# Domino_USB_MicroSD_Passive_Overcurrent_P.net
KiCad netlist of a schematic drawn in EAGLE
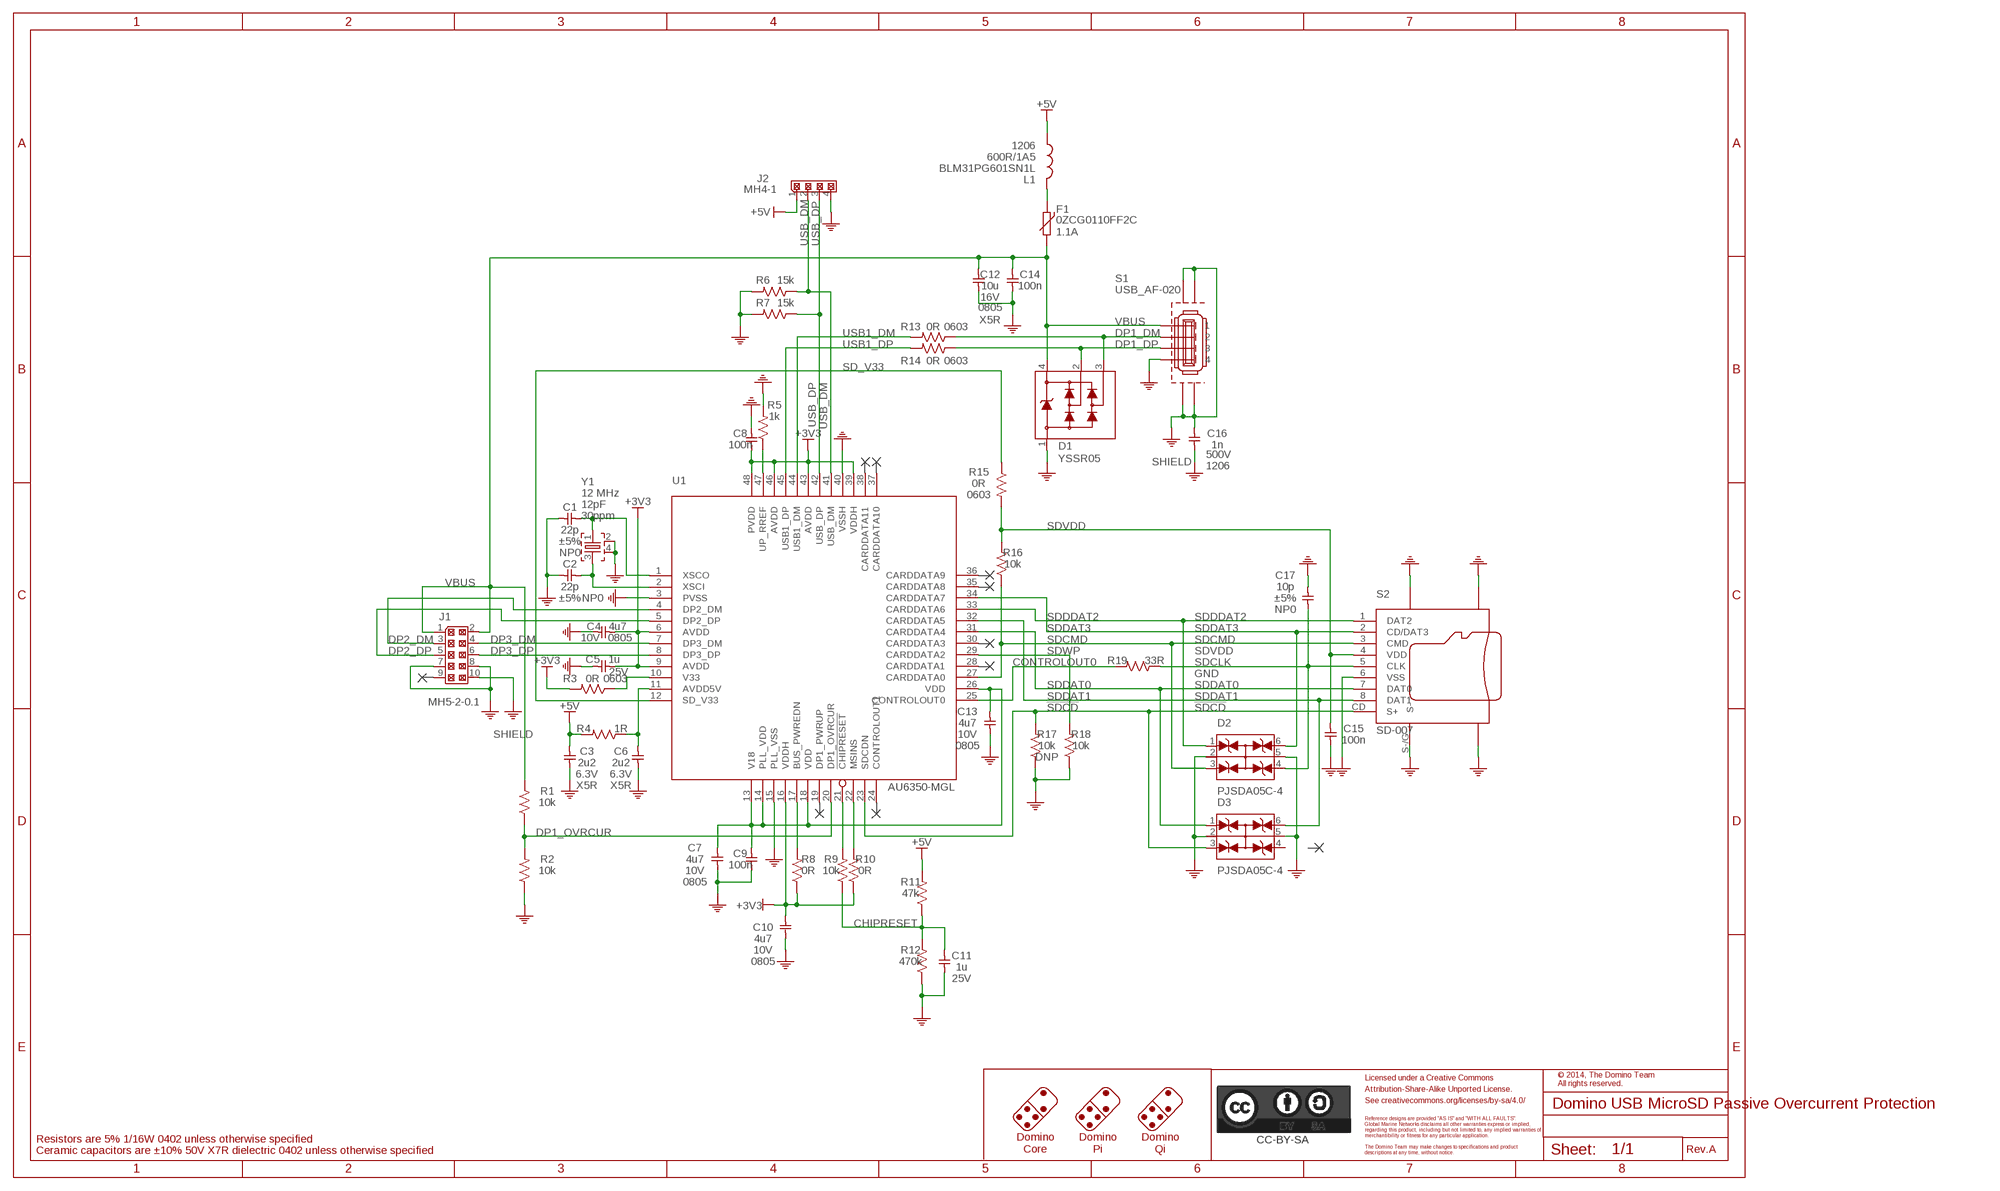
[diagram p0: schematic, sheet 1]

(export (version "E")
  (design (tool "Eeschema 10.0.6"))
  (components
    (comp (ref "C1")
      (value "22p")
      (footprint "eagle-import:C0402")
      (fields
        (field (name "PARTNO") "C0402_22p_NP0_5%_CER_50V")
        (field (name "TC") "NP0")
        (field (name "TOL") "±5%")
      )
      (libsource (lib "eagle-import") (part "CAP_0402"))
    )
    (comp (ref "C2")
      (value "22p")
      (footprint "eagle-import:C0402")
      (fields
        (field (name "PARTNO") "C0402_22p_NP0_5%_CER_50V")
        (field (name "TC") "NP0")
        (field (name "TOL") "±5%")
      )
      (libsource (lib "eagle-import") (part "CAP_0402"))
    )
    (comp (ref "C3")
      (value "2u2")
      (footprint "eagle-import:C0402")
      (fields
        (field (name "PARTNO") "C0402_2u2_X5R_10%_CER_6V3")
        (field (name "TC") "X5R")
        (field (name "VOLT") "6.3V")
      )
      (libsource (lib "eagle-import") (part "CAP_0402"))
    )
    (comp (ref "C4")
      (value "4u7")
      (footprint "eagle-import:C0805")
      (fields
        (field (name "SIZE") "0805")
        (field (name "PARTNO") "C0805_4u7_X7R_10%_CER_6V3")
        (field (name "VOLT") "10V")
      )
      (libsource (lib "eagle-import") (part "CAP_0805"))
    )
    (comp (ref "C5")
      (value "1u")
      (footprint "eagle-import:C0402")
      (fields (field (name "PARTNO") "C0402_1u_X7R_10%_CER_25V") (field (name "VOLT") "25V"))
      (libsource (lib "eagle-import") (part "CAP_0402"))
    )
    (comp (ref "C6")
      (value "2u2")
      (footprint "eagle-import:C0402")
      (fields
        (field (name "PARTNO") "C0402_2u2_X5R_10%_CER_6V3")
        (field (name "TC") "X5R")
        (field (name "VOLT") "6.3V")
      )
      (libsource (lib "eagle-import") (part "CAP_0402"))
    )
    (comp (ref "C7")
      (value "4u7")
      (footprint "eagle-import:C0805")
      (fields
        (field (name "SIZE") "0805")
        (field (name "PARTNO") "C0805_4u7_X7R_10%_CER_6V3")
        (field (name "VOLT") "10V")
      )
      (libsource (lib "eagle-import") (part "CAP_0805"))
    )
    (comp (ref "C8")
      (value "100n")
      (footprint "eagle-import:C0402")
      (fields (field (name "PARTNO") "C0402_100n_X7R_10%_CER_50V"))
      (libsource (lib "eagle-import") (part "CAP_0402"))
    )
    (comp (ref "C9")
      (value "100n")
      (footprint "eagle-import:C0402")
      (fields (field (name "PARTNO") "C0402_100n_X7R_10%_CER_50V"))
      (libsource (lib "eagle-import") (part "CAP_0402"))
    )
    (comp (ref "C10")
      (value "4u7")
      (footprint "eagle-import:C0805")
      (fields
        (field (name "SIZE") "0805")
        (field (name "PARTNO") "C0805_4u7_X7R_10%_CER_6V3")
        (field (name "VOLT") "10V")
      )
      (libsource (lib "eagle-import") (part "CAP_0805"))
    )
    (comp (ref "C11")
      (value "1u")
      (footprint "eagle-import:C0402")
      (fields (field (name "PARTNO") "C0402_1u_X7R_10%_CER_25V") (field (name "VOLT") "25V"))
      (libsource (lib "eagle-import") (part "CAP_0402"))
    )
    (comp (ref "C12")
      (value "10u")
      (footprint "eagle-import:C0805")
      (fields
        (field (name "SIZE") "0805")
        (field (name "PARTNO") "C0805_10u_X5R_10%_CER_16V")
        (field (name "TC") "X5R")
        (field (name "VOLT") "16V")
      )
      (libsource (lib "eagle-import") (part "CAP_0805"))
    )
    (comp (ref "C13")
      (value "4u7")
      (footprint "eagle-import:C0805")
      (fields
        (field (name "SIZE") "0805")
        (field (name "PARTNO") "C0805_4u7_X7R_10%_CER_6V3")
        (field (name "VOLT") "10V")
      )
      (libsource (lib "eagle-import") (part "CAP_0805"))
    )
    (comp (ref "C14")
      (value "100n")
      (footprint "eagle-import:C0402")
      (fields (field (name "PARTNO") "C0402_100n_X7R_10%_CER_50V"))
      (libsource (lib "eagle-import") (part "CAP_0402"))
    )
    (comp (ref "C15")
      (value "100n")
      (footprint "eagle-import:C0402")
      (fields (field (name "PARTNO") "C0402_100n_X7R_10%_CER_50V"))
      (libsource (lib "eagle-import") (part "CAP_0402"))
    )
    (comp (ref "C16")
      (value "1n")
      (footprint "eagle-import:C1206")
      (fields
        (field (name "SIZE") "1206")
        (field (name "PARTNO") "C1206_1n_X7R_10%_CER_500V")
        (field (name "VOLT") "500V")
      )
      (libsource (lib "eagle-import") (part "CAP_1206"))
    )
    (comp (ref "C17")
      (value "10p")
      (footprint "eagle-import:C0402")
      (fields
        (field (name "PARTNO") "C0402_10p_NP0_5%_CER_50V")
        (field (name "TC") "NP0")
        (field (name "TOL") "±5%")
      )
      (libsource (lib "eagle-import") (part "CAP_0402"))
    )
    (comp (ref "CC-BY-SA1")
      (value "CC-BY-SA_LOGO")
      (footprint "eagle-import:CC-BY-SA_LOGO")
      (libsource (lib "eagle-import") (part "CC-BY-SA_LOGO"))
    )
    (comp (ref "D1")
      (value "YSSR05")
      (footprint "eagle-import:SOT143B")
      (libsource (lib "eagle-import") (part "YSSR05"))
    )
    (comp (ref "D2")
      (value "PJSDA05C-4")
      (footprint "eagle-import:SOT23-6")
      (libsource (lib "eagle-import") (part "PJSDA05C-4"))
    )
    (comp (ref "D3")
      (value "PJSDA05C-4")
      (footprint "eagle-import:SOT23-6")
      (libsource (lib "eagle-import") (part "PJSDA05C-4"))
    )
    (comp (ref "F1")
      (value "0ZCG0110FF2C")
      (footprint "eagle-import:PTC1812")
      (fields (field (name "RATE") "1.1A"))
      (libsource (lib "eagle-import") (part "0ZCG0110FF2C"))
    )
    (comp (ref "J1")
      (value "MH5-2-0.1")
      (footprint "eagle-import:MH05-2-0.1")
      (libsource (lib "eagle-import") (part "MH5-2"))
    )
    (comp (ref "J2")
      (value "MH4-1")
      (footprint "eagle-import:MH4-1-0.1")
      (fields (field (name "PARTNO") "MH4-1-0.1"))
      (libsource (lib "eagle-import") (part "MH4-1"))
    )
    (comp (ref "L1")
      (value "BLM31PG601SN1L")
      (footprint "eagle-import:FB1206")
      (fields (field (name "SIZE") "1206") (field (name "OPT") "600R/1A5"))
      (libsource (lib "eagle-import") (part "FB_1206"))
    )
    (comp (ref "R1")
      (value "10k")
      (footprint "eagle-import:R0402")
      (fields (field (name "PARTNO") "R0402_10k_5%_62.5mW"))
      (libsource (lib "eagle-import") (part "RES_0402"))
    )
    (comp (ref "R2")
      (value "10k")
      (footprint "eagle-import:R0402")
      (fields (field (name "PARTNO") "R0402_10k_5%_62.5mW"))
      (libsource (lib "eagle-import") (part "RES_0402"))
    )
    (comp (ref "R3")
      (value "0R")
      (footprint "eagle-import:R0603")
      (fields (field (name "SIZE") "0603") (field (name "PARTNO") "R0603_0R_5%_125mW"))
      (libsource (lib "eagle-import") (part "RES_0603"))
    )
    (comp (ref "R4")
      (value "1R")
      (footprint "eagle-import:R0402")
      (fields (field (name "PARTNO") "R0402_1R_5%_62.5mW"))
      (libsource (lib "eagle-import") (part "RES_0402"))
    )
    (comp (ref "R5")
      (value "1k")
      (footprint "eagle-import:R0402")
      (fields (field (name "PARTNO") "R0402_1k_5%_62.5mW"))
      (libsource (lib "eagle-import") (part "RES_0402"))
    )
    (comp (ref "R6")
      (value "15k")
      (footprint "eagle-import:R0402")
      (fields (field (name "PARTNO") "R0402_15k_5%_62.5mW"))
      (libsource (lib "eagle-import") (part "RES_0402"))
    )
    (comp (ref "R7")
      (value "15k")
      (footprint "eagle-import:R0402")
      (fields (field (name "PARTNO") "R0402_15k_5%_62.5mW"))
      (libsource (lib "eagle-import") (part "RES_0402"))
    )
    (comp (ref "R8")
      (value "0R")
      (footprint "eagle-import:R0402")
      (fields (field (name "PARTNO") "R0402_0R_5%_62.5mW"))
      (libsource (lib "eagle-import") (part "RES_0402"))
    )
    (comp (ref "R9")
      (value "10k")
      (footprint "eagle-import:R0402")
      (fields (field (name "PARTNO") "R0402_10k_5%_62.5mW"))
      (libsource (lib "eagle-import") (part "RES_0402"))
    )
    (comp (ref "R10")
      (value "0R")
      (footprint "eagle-import:R0402")
      (fields (field (name "PARTNO") "R0402_0R_5%_62.5mW"))
      (libsource (lib "eagle-import") (part "RES_0402"))
    )
    (comp (ref "R11")
      (value "47k")
      (footprint "eagle-import:R0402")
      (fields (field (name "PARTNO") "R0402_47k_5%_62.5mW"))
      (libsource (lib "eagle-import") (part "RES_0402"))
    )
    (comp (ref "R12")
      (value "470k")
      (footprint "eagle-import:R0402")
      (fields (field (name "PARTNO") "R0402_470k_5%_62.5mW"))
      (libsource (lib "eagle-import") (part "RES_0402"))
    )
    (comp (ref "R13")
      (value "0R")
      (footprint "eagle-import:R0603")
      (fields (field (name "SIZE") "0603") (field (name "PARTNO") "R0603_0R_5%_125mW"))
      (libsource (lib "eagle-import") (part "RES_0603"))
    )
    (comp (ref "R14")
      (value "0R")
      (footprint "eagle-import:R0603")
      (fields (field (name "SIZE") "0603") (field (name "PARTNO") "R0603_0R_5%_125mW"))
      (libsource (lib "eagle-import") (part "RES_0603"))
    )
    (comp (ref "R15")
      (value "0R")
      (footprint "eagle-import:R0603")
      (fields (field (name "SIZE") "0603") (field (name "PARTNO") "R0603_0R_5%_125mW"))
      (libsource (lib "eagle-import") (part "RES_0603"))
    )
    (comp (ref "R16")
      (value "10k")
      (footprint "eagle-import:R0402")
      (fields (field (name "PARTNO") "R0402_10k_5%_62.5mW"))
      (libsource (lib "eagle-import") (part "RES_0402"))
    )
    (comp (ref "R17")
      (value "10k")
      (footprint "eagle-import:R0402")
      (fields (field (name "PARTNO") "R0402_10k_5%_62.5mW"))
      (libsource (lib "eagle-import") (part "RES_0402"))
    )
    (comp (ref "R18")
      (value "10k")
      (footprint "eagle-import:R0402")
      (fields (field (name "PARTNO") "R0402_10k_5%_62.5mW"))
      (libsource (lib "eagle-import") (part "RES_0402"))
    )
    (comp (ref "R19")
      (value "33R")
      (footprint "eagle-import:R0402")
      (fields (field (name "PARTNO") "R0402_33R_5%_62.5mW"))
      (libsource (lib "eagle-import") (part "RES_0402"))
    )
    (comp (ref "S1")
      (value "USB_AF-020")
      (footprint "eagle-import:USB_AF-020")
      (libsource (lib "eagle-import") (part "USB_AF-020"))
    )
    (comp (ref "S2")
      (value "SD-007")
      (footprint "eagle-import:SD-007")
      (libsource (lib "eagle-import") (part "MICRO-SD"))
    )
    (comp (ref "U1")
      (value "AU6350-MGL")
      (footprint "eagle-import:LQFP-48_7X7")
      (libsource (lib "eagle-import") (part "AU6350-MGL"))
    )
    (comp (ref "Y1")
      (value "12 MHz")
      (footprint "eagle-import:CRYSTAL_32X25")
      (fields
        (field (name "LOAD") "12pF")
        (field (name "PARTNO") "CRYSTAL_32X25_2SH_12PF_30PPM")
        (field (name "TOL") "30ppm")
      )
      (libsource (lib "eagle-import") (part "CRYSTAL_2SH"))
    )
  )
  (nets
    (net (code "1") (name "+3V3") (class "Default")
      (node (ref "C10") (pin "2") (pinfunction "2_2") (pintype "passive"))
      (node (ref "C4") (pin "2") (pinfunction "2_2") (pintype "passive"))
      (node (ref "C5") (pin "2") (pinfunction "2_2") (pintype "passive"))
      (node (ref "C8") (pin "2") (pinfunction "2_2") (pintype "passive"))
      (node (ref "R10") (pin "1") (pinfunction "1_1") (pintype "passive"))
      (node (ref "R3") (pin "2") (pinfunction "2_2") (pintype "passive"))
      (node (ref "R8") (pin "1") (pinfunction "1_1") (pintype "passive"))
      (node (ref "U1") (pin "16") (pinfunction "VDDH_16") (pintype "power_in"))
      (node (ref "U1") (pin "39") (pinfunction "VDDH_39") (pintype "power_in"))
      (node (ref "U1") (pin "43") (pinfunction "AVDD_43") (pintype "power_in"))
      (node (ref "U1") (pin "46") (pinfunction "AVDD_46") (pintype "power_in"))
      (node (ref "U1") (pin "48") (pinfunction "PVDD_48") (pintype "power_in"))
      (node (ref "U1") (pin "6") (pinfunction "AVDD_6") (pintype "power_in"))
      (node (ref "U1") (pin "9") (pinfunction "AVDD_9") (pintype "power_in"))
    )
    (net (code "2") (name "+5V") (class "Default")
      (node (ref "C3") (pin "1") (pinfunction "1_1") (pintype "passive"))
      (node (ref "J2") (pin "1") (pinfunction "1_1") (pintype "passive"))
      (node (ref "L1") (pin "2") (pinfunction "2_2") (pintype "passive"))
      (node (ref "R11") (pin "2") (pinfunction "2_2") (pintype "passive"))
      (node (ref "R4") (pin "2") (pinfunction "2_2") (pintype "passive"))
    )
    (net (code "3") (name "/CHIPRESET") (class "Default")
      (node (ref "C11") (pin "1") (pinfunction "1_1") (pintype "passive"))
      (node (ref "R11") (pin "1") (pinfunction "1_1") (pintype "passive"))
      (node (ref "R12") (pin "2") (pinfunction "2_2") (pintype "passive"))
      (node (ref "R9") (pin "1") (pinfunction "1_1") (pintype "passive"))
    )
    (net (code "4") (name "/CONTROLOUT0") (class "Default")
      (node (ref "R19") (pin "2") (pinfunction "2_2") (pintype "passive"))
      (node (ref "U1") (pin "25") (pinfunction "CONTROLOUT0_25") (pintype "output"))
    )
    (net (code "5") (name "/DP1_DM") (class "Default")
      (node (ref "D1") (pin "3") (pinfunction "P$3_3") (pintype "passive"))
      (node (ref "R13") (pin "1") (pinfunction "1_1") (pintype "passive"))
      (node (ref "S1") (pin "2") (pinfunction "2_2") (pintype "passive"))
    )
    (net (code "6") (name "/DP1_DP") (class "Default")
      (node (ref "D1") (pin "2") (pinfunction "P$2_2") (pintype "passive"))
      (node (ref "R14") (pin "1") (pinfunction "1_1") (pintype "passive"))
      (node (ref "S1") (pin "3") (pinfunction "3_3") (pintype "passive"))
    )
    (net (code "7") (name "/DP1_OVRCUR") (class "Default")
      (node (ref "R1") (pin "1") (pinfunction "1_1") (pintype "passive"))
      (node (ref "R2") (pin "2") (pinfunction "2_2") (pintype "passive"))
      (node (ref "U1") (pin "20") (pinfunction "DP1_OVRCUR_20") (pintype "input"))
    )
    (net (code "8") (name "/DP2_DM") (class "Default")
      (node (ref "J1") (pin "3") (pinfunction "3_3") (pintype "passive"))
      (node (ref "U1") (pin "4") (pinfunction "DP2_DM_4") (pintype "passive"))
    )
    (net (code "9") (name "/DP2_DP") (class "Default")
      (node (ref "J1") (pin "5") (pinfunction "5_5") (pintype "passive"))
      (node (ref "U1") (pin "5") (pinfunction "DP2_DP_5") (pintype "passive"))
    )
    (net (code "10") (name "/DP3_DM") (class "Default")
      (node (ref "J1") (pin "4") (pinfunction "4_4") (pintype "passive"))
      (node (ref "U1") (pin "7") (pinfunction "DP3_DM_7") (pintype "passive"))
    )
    (net (code "11") (name "/DP3_DP") (class "Default")
      (node (ref "J1") (pin "6") (pinfunction "6_6") (pintype "passive"))
      (node (ref "U1") (pin "8") (pinfunction "DP3_DP_8") (pintype "passive"))
    )
    (net (code "12") (name "/SDCLK") (class "Default")
      (node (ref "C17") (pin "1") (pinfunction "1_1") (pintype "passive"))
      (node (ref "D2") (pin "4") (pinfunction "4_4") (pintype "passive"))
      (node (ref "R19") (pin "1") (pinfunction "1_1") (pintype "passive"))
      (node (ref "S2") (pin "5") (pinfunction "CLK_5") (pintype "input"))
    )
    (net (code "13") (name "/SDCMD") (class "Default")
      (node (ref "D2") (pin "3") (pinfunction "3_3") (pintype "passive"))
      (node (ref "R16") (pin "1") (pinfunction "1_1") (pintype "passive"))
      (node (ref "S2") (pin "3") (pinfunction "CMD_3") (pintype "input"))
      (node (ref "U1") (pin "27") (pinfunction "CARDDATA0_27") (pintype "bidirectional"))
    )
    (net (code "14") (name "/SDDAT0") (class "Default")
      (node (ref "D3") (pin "1") (pinfunction "1_1") (pintype "passive"))
      (node (ref "S2") (pin "7") (pinfunction "DAT0_7") (pintype "bidirectional"))
      (node (ref "U1") (pin "31") (pinfunction "CARDDATA4_31") (pintype "bidirectional"))
    )
    (net (code "15") (name "/SDDAT1") (class "Default")
      (node (ref "D3") (pin "6") (pinfunction "6_6") (pintype "passive"))
      (node (ref "S2") (pin "8") (pinfunction "DAT1_8") (pintype "bidirectional"))
      (node (ref "U1") (pin "32") (pinfunction "CARDDATA5_32") (pintype "bidirectional"))
    )
    (net (code "16") (name "/SDDAT3") (class "Default")
      (node (ref "D2") (pin "6") (pinfunction "6_6") (pintype "passive"))
      (node (ref "S2") (pin "2") (pinfunction "CD/DAT3_2") (pintype "bidirectional"))
      (node (ref "U1") (pin "34") (pinfunction "CARDDATA7_34") (pintype "bidirectional"))
    )
    (net (code "17") (name "/SDDDAT2") (class "Default")
      (node (ref "D2") (pin "1") (pinfunction "1_1") (pintype "passive"))
      (node (ref "S2") (pin "1") (pinfunction "DAT2_1") (pintype "bidirectional"))
      (node (ref "U1") (pin "33") (pinfunction "CARDDATA6_33") (pintype "bidirectional"))
    )
    (net (code "18") (name "/SDVDD") (class "Default")
      (node (ref "C15") (pin "1") (pinfunction "1_1") (pintype "passive"))
      (node (ref "R15") (pin "2") (pinfunction "2_2") (pintype "passive"))
      (node (ref "R16") (pin "2") (pinfunction "2_2") (pintype "passive"))
      (node (ref "S2") (pin "4") (pinfunction "VDD_4") (pintype "power_in"))
    )
    (net (code "19") (name "/SDWP") (class "Default")
      (node (ref "R18") (pin "2") (pinfunction "2_2") (pintype "passive"))
      (node (ref "U1") (pin "29") (pinfunction "CARDDATA2_29") (pintype "bidirectional"))
    )
    (net (code "20") (name "/SD_V33") (class "Default")
      (node (ref "R15") (pin "1") (pinfunction "1_1") (pintype "passive"))
      (node (ref "U1") (pin "12") (pinfunction "SD_V33_12") (pintype "power_in"))
    )
    (net (code "21") (name "/USB1_DM") (class "Default")
      (node (ref "R13") (pin "2") (pinfunction "2_2") (pintype "passive"))
      (node (ref "U1") (pin "44") (pinfunction "USB1_DM_44") (pintype "passive"))
    )
    (net (code "22") (name "/USB1_DP") (class "Default")
      (node (ref "R14") (pin "2") (pinfunction "2_2") (pintype "passive"))
      (node (ref "U1") (pin "45") (pinfunction "USB1_DP_45") (pintype "passive"))
    )
    (net (code "23") (name "/USB_DM") (class "Default")
      (node (ref "J2") (pin "2") (pinfunction "2_2") (pintype "passive"))
      (node (ref "R6") (pin "1") (pinfunction "1_1") (pintype "passive"))
      (node (ref "U1") (pin "41") (pinfunction "USB_DM_41") (pintype "passive"))
    )
    (net (code "24") (name "/USB_DP") (class "Default")
      (node (ref "J2") (pin "3") (pinfunction "3_3") (pintype "passive"))
      (node (ref "R7") (pin "1") (pinfunction "1_1") (pintype "passive"))
      (node (ref "U1") (pin "42") (pinfunction "USB_DP_42") (pintype "passive"))
    )
    (net (code "25") (name "/VBUS") (class "Default")
      (node (ref "C12") (pin "1") (pinfunction "1_1") (pintype "passive"))
      (node (ref "C14") (pin "1") (pinfunction "1_1") (pintype "passive"))
      (node (ref "D1") (pin "4") (pinfunction "P$4_4") (pintype "passive"))
      (node (ref "F1") (pin "2") (pinfunction "2_2") (pintype "passive"))
      (node (ref "J1") (pin "1") (pinfunction "1_1") (pintype "passive"))
      (node (ref "J1") (pin "2") (pinfunction "2_2") (pintype "passive"))
      (node (ref "R1") (pin "2") (pinfunction "2_2") (pintype "passive"))
      (node (ref "S1") (pin "1") (pinfunction "1_1") (pintype "passive"))
    )
    (net (code "26") (name "/~{SDCD}") (class "Default")
      (node (ref "D3") (pin "3") (pinfunction "3_3") (pintype "passive"))
      (node (ref "R17") (pin "2") (pinfunction "2_2") (pintype "passive"))
      (node (ref "S2") (pin "CD") (pinfunction "S+_CD") (pintype "output"))
      (node (ref "U1") (pin "23") (pinfunction "SDCDN_23") (pintype "input"))
    )
    (net (code "27") (name "GND") (class "Default")
      (node (ref "C1") (pin "1") (pinfunction "1_1") (pintype "passive"))
      (node (ref "C10") (pin "1") (pinfunction "1_1") (pintype "passive"))
      (node (ref "C11") (pin "2") (pinfunction "2_2") (pintype "passive"))
      (node (ref "C12") (pin "2") (pinfunction "2_2") (pintype "passive"))
      (node (ref "C13") (pin "1") (pinfunction "1_1") (pintype "passive"))
      (node (ref "C14") (pin "2") (pinfunction "2_2") (pintype "passive"))
      (node (ref "C15") (pin "2") (pinfunction "2_2") (pintype "passive"))
      (node (ref "C16") (pin "2") (pinfunction "2_2") (pintype "passive"))
      (node (ref "C17") (pin "2") (pinfunction "2_2") (pintype "passive"))
      (node (ref "C2") (pin "1") (pinfunction "1_1") (pintype "passive"))
      (node (ref "C3") (pin "2") (pinfunction "2_2") (pintype "passive"))
      (node (ref "C4") (pin "1") (pinfunction "1_1") (pintype "passive"))
      (node (ref "C5") (pin "1") (pinfunction "1_1") (pintype "passive"))
      (node (ref "C6") (pin "2") (pinfunction "2_2") (pintype "passive"))
      (node (ref "C7") (pin "1") (pinfunction "1_1") (pintype "passive"))
      (node (ref "C8") (pin "1") (pinfunction "1_1") (pintype "passive"))
      (node (ref "C9") (pin "2") (pinfunction "2_2") (pintype "passive"))
      (node (ref "D1") (pin "1") (pinfunction "P$1_1") (pintype "passive"))
      (node (ref "D2") (pin "2") (pinfunction "2_2") (pintype "passive"))
      (node (ref "D2") (pin "5") (pinfunction "5_5") (pintype "passive"))
      (node (ref "D3") (pin "2") (pinfunction "2_2") (pintype "passive"))
      (node (ref "D3") (pin "5") (pinfunction "5_5") (pintype "passive"))
      (node (ref "J1") (pin "7") (pinfunction "7_7") (pintype "passive"))
      (node (ref "J1") (pin "8") (pinfunction "8_8") (pintype "passive"))
      (node (ref "J2") (pin "4") (pinfunction "4_4") (pintype "passive"))
      (node (ref "R12") (pin "1") (pinfunction "1_1") (pintype "passive"))
      (node (ref "R17") (pin "1") (pinfunction "1_1") (pintype "passive"))
      (node (ref "R18") (pin "1") (pinfunction "1_1") (pintype "passive"))
      (node (ref "R2") (pin "1") (pinfunction "1_1") (pintype "passive"))
      (node (ref "R5") (pin "2") (pinfunction "2_2") (pintype "passive"))
      (node (ref "R6") (pin "2") (pinfunction "2_2") (pintype "passive"))
      (node (ref "R7") (pin "2") (pinfunction "2_2") (pintype "passive"))
      (node (ref "S1") (pin "4") (pinfunction "4_4") (pintype "passive"))
      (node (ref "S2") (pin "6") (pinfunction "VSS_6") (pintype "power_in"))
      (node (ref "S2") (pin "G$1") (pinfunction "G_G$1") (pintype "power_in"))
      (node (ref "S2") (pin "G$2") (pinfunction "G_G$2") (pintype "power_in"))
      (node (ref "S2") (pin "G$3") (pinfunction "G_G$3") (pintype "power_in"))
      (node (ref "S2") (pin "S-/G") (pinfunction "S-_S-/G") (pintype "power_in"))
      (node (ref "U1") (pin "15") (pinfunction "PLL_VSS_15") (pintype "power_in"))
      (node (ref "U1") (pin "3") (pinfunction "PVSS_3") (pintype "power_in"))
      (node (ref "U1") (pin "40") (pinfunction "VSSH_40") (pintype "power_in"))
      (node (ref "Y1") (pin "2") (pinfunction "2_2") (pintype "passive"))
      (node (ref "Y1") (pin "4") (pinfunction "4_4") (pintype "passive"))
    )
    (net (code "28") (name "Net-(F1-Pad1)") (class "Default")
      (node (ref "F1") (pin "1") (pinfunction "1_1") (pintype "passive"))
      (node (ref "L1") (pin "1") (pinfunction "1_1") (pintype "passive"))
    )
    (net (code "29") (name "Net-(U1-AVDD5V)") (class "Default")
      (node (ref "C6") (pin "1") (pinfunction "1_1") (pintype "passive"))
      (node (ref "R4") (pin "1") (pinfunction "1_1") (pintype "passive"))
      (node (ref "U1") (pin "11") (pinfunction "AVDD5V_11") (pintype "power_in"))
    )
    (net (code "30") (name "Net-(U1-BUS_PWREDN)") (class "Default")
      (node (ref "R8") (pin "2") (pinfunction "2_2") (pintype "passive"))
      (node (ref "U1") (pin "17") (pinfunction "BUS_PWREDN_17") (pintype "input"))
    )
    (net (code "31") (name "Net-(U1-MSINS)") (class "Default")
      (node (ref "R10") (pin "2") (pinfunction "2_2") (pintype "passive"))
      (node (ref "U1") (pin "22") (pinfunction "MSINS_22") (pintype "input"))
    )
    (net (code "32") (name "Net-(U1-PLL_VDD)") (class "Default")
      (node (ref "C13") (pin "2") (pinfunction "2_2") (pintype "passive"))
      (node (ref "C7") (pin "2") (pinfunction "2_2") (pintype "passive"))
      (node (ref "C9") (pin "1") (pinfunction "1_1") (pintype "passive"))
      (node (ref "U1") (pin "13") (pinfunction "V18_13") (pintype "power_in"))
      (node (ref "U1") (pin "14") (pinfunction "PLL_VDD_14") (pintype "power_in"))
      (node (ref "U1") (pin "18") (pinfunction "VDD_18") (pintype "power_in"))
      (node (ref "U1") (pin "26") (pinfunction "VDD_26") (pintype "power_in"))
    )
    (net (code "33") (name "Net-(U1-UP_RREF)") (class "Default")
      (node (ref "R5") (pin "1") (pinfunction "1_1") (pintype "passive"))
      (node (ref "U1") (pin "47") (pinfunction "UP_RREF_47") (pintype "passive"))
    )
    (net (code "34") (name "Net-(U1-V33)") (class "Default")
      (node (ref "R3") (pin "1") (pinfunction "1_1") (pintype "passive"))
      (node (ref "U1") (pin "10") (pinfunction "V33_10") (pintype "power_in"))
    )
    (net (code "35") (name "Net-(U1-XSCI)") (class "Default")
      (node (ref "C2") (pin "2") (pinfunction "2_2") (pintype "passive"))
      (node (ref "U1") (pin "2") (pinfunction "XSCI_2") (pintype "passive"))
      (node (ref "Y1") (pin "3") (pinfunction "3_3") (pintype "passive"))
    )
    (net (code "36") (name "Net-(U1-XSCO)") (class "Default")
      (node (ref "C1") (pin "2") (pinfunction "2_2") (pintype "passive"))
      (node (ref "U1") (pin "1") (pinfunction "XSCO_1") (pintype "passive"))
      (node (ref "Y1") (pin "1") (pinfunction "1_1") (pintype "passive"))
    )
    (net (code "37") (name "Net-(U1-~{CHIPRESET})") (class "Default")
      (node (ref "R9") (pin "2") (pinfunction "2_2") (pintype "passive"))
      (node (ref "U1") (pin "21") (pinfunction "~{CHIPRESET}_21") (pintype "input"))
    )
    (net (code "38") (name "SHIELD") (class "Default")
      (node (ref "C16") (pin "1") (pinfunction "1_1") (pintype "passive"))
      (node (ref "J1") (pin "10") (pinfunction "10_10") (pintype "passive"))
      (node (ref "S1") (pin "G$1") (pinfunction "G_G$1") (pintype "passive"))
      (node (ref "S1") (pin "G$2") (pinfunction "G_G$2") (pintype "passive"))
      (node (ref "S1") (pin "G$3") (pinfunction "G_G$3") (pintype "passive"))
      (node (ref "S1") (pin "G$4") (pinfunction "G_G$4") (pintype "passive"))
    )
    (net (code "39") (name "unconnected-(D3-Pad4)") (class "Default")
      (node (ref "D3") (pin "4") (pinfunction "4_4") (pintype "passive"))
    )
    (net (code "40") (name "unconnected-(J1-Pad9)") (class "Default")
      (node (ref "J1") (pin "9") (pinfunction "9_9") (pintype "passive"))
    )
    (net (code "41") (name "unconnected-(U1-CARDDATA1-Pad28)") (class "Default")
      (node (ref "U1") (pin "28") (pinfunction "CARDDATA1_28") (pintype "bidirectional"))
    )
    (net (code "42") (name "unconnected-(U1-CARDDATA3-Pad30)") (class "Default")
      (node (ref "U1") (pin "30") (pinfunction "CARDDATA3_30") (pintype "bidirectional"))
    )
    (net (code "43") (name "unconnected-(U1-CARDDATA8-Pad35)") (class "Default")
      (node (ref "U1") (pin "35") (pinfunction "CARDDATA8_35") (pintype "bidirectional"))
    )
    (net (code "44") (name "unconnected-(U1-CARDDATA9-Pad36)") (class "Default")
      (node (ref "U1") (pin "36") (pinfunction "CARDDATA9_36") (pintype "bidirectional"))
    )
    (net (code "45") (name "unconnected-(U1-CARDDATA10-Pad37)") (class "Default")
      (node (ref "U1") (pin "37") (pinfunction "CARDDATA10_37") (pintype "bidirectional"))
    )
    (net (code "46") (name "unconnected-(U1-CARDDATA11-Pad38)") (class "Default")
      (node (ref "U1") (pin "38") (pinfunction "CARDDATA11_38") (pintype "bidirectional"))
    )
    (net (code "47") (name "unconnected-(U1-CONTROLOUT1-Pad24)") (class "Default")
      (node (ref "U1") (pin "24") (pinfunction "CONTROLOUT1_24") (pintype "output"))
    )
    (net (code "48") (name "unconnected-(U1-DP1_PWRUP-Pad19)") (class "Default")
      (node (ref "U1") (pin "19") (pinfunction "DP1_PWRUP_19") (pintype "output"))
    )
  )
)
